# watchdog.net
KiCad netlist of a schematic drawn in Altium Designer
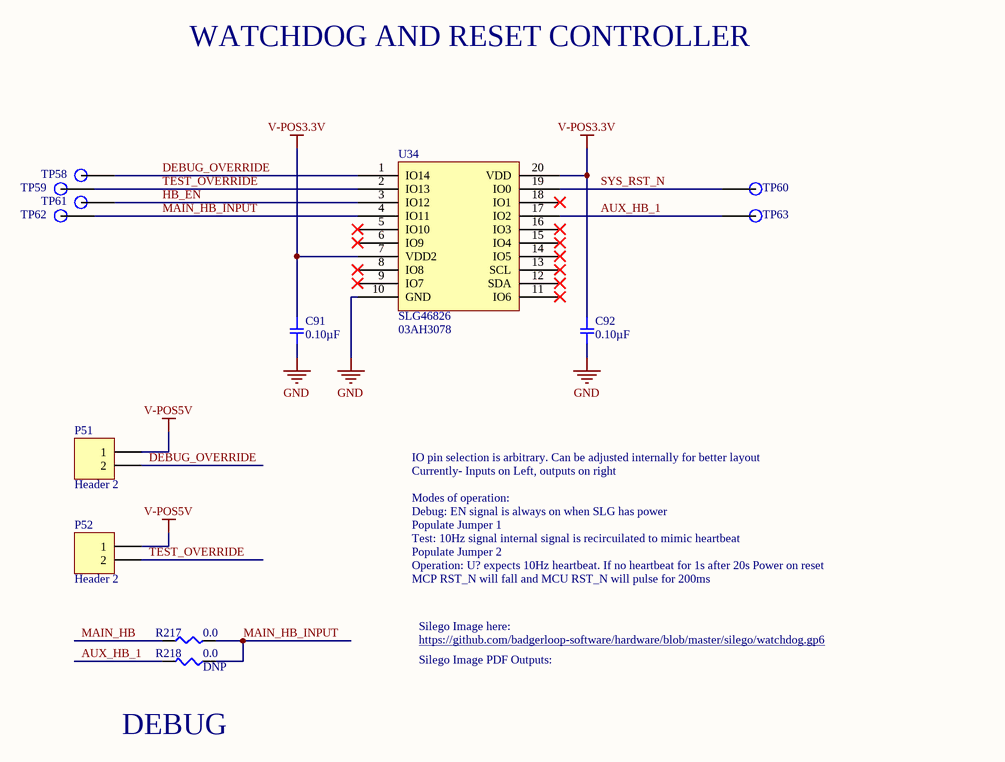
[diagram p0: watchdog.SchDoc]

(export (version "E")
  (design (tool "Eeschema 10.0.6"))
  (components
    (comp (ref "C91")
      (value "0.10µF")
      (footprint "SMD-0805C")
      (description "CAP CER 0.1UF 25V X7R 0805")
      (fields
        (field (name "DIGI-KEY PART NUMBER") "490-12754-1-ND")
        (field (name "PART NUMBER") "GRM219R71E104KA01D")
      )
      (libsource (lib "capacitors") (part "GRM219R71E104KA01D"))
    )
    (comp (ref "C92")
      (value "0.10µF")
      (footprint "SMD-0805C")
      (description "CAP CER 0.1UF 25V X7R 0805")
      (fields
        (field (name "DIGI-KEY PART NUMBER") "490-12754-1-ND")
        (field (name "PART NUMBER") "GRM219R71E104KA01D")
      )
      (libsource (lib "capacitors") (part "GRM219R71E104KA01D"))
    )
    (comp (ref "P51")
      (value "Header 2")
      (footprint "Pin Header 1x2 TH Pitch 2.54mm")
      (description "Header, 2-Pin")
      (fields (field (name "PUBLISHER") "Altium Limited"))
      (libsource (lib "connector") (part "Header 2"))
    )
    (comp (ref "P52")
      (value "Header 2")
      (footprint "Pin Header 1x2 TH Pitch 2.54mm")
      (description "Header, 2-Pin")
      (fields (field (name "PUBLISHER") "Altium Limited"))
      (libsource (lib "connector") (part "Header 2"))
    )
    (comp (ref "R217")
      (value "0.0")
      (footprint "SMD-0805-RES")
      (description "RES SMD 0.0 OHM JUMPER 1/8W 0805")
      (fields (field (name "PART NUMBER") "ERJ-6GEY0R00V") (field (name "DIGI-KEY PART NUMBER") "P0.0ACT-ND"))
      (libsource (lib "resistors") (part "ERJ-6GEY0R00V"))
    )
    (comp (ref "R218")
      (value "0.0")
      (footprint "SMD-0805-RES")
      (description "RES SMD 0.0 OHM JUMPER 1/8W 0805")
      (fields
        (field (name "PART NUMBER") "ERJ-6GEY0R00V")
        (field (name "DIGI-KEY PART NUMBER") "P0.0ACT-ND")
        (field (name "DNP") "DNP")
      )
      (libsource (lib "resistors") (part "ERJ-6GEY0R00V"))
    )
    (comp (ref "TP58")
      (value "TP")
      (footprint "Test Point")
      (description "SMD TEST POINT")
      (libsource (lib "misc") (part "TP"))
    )
    (comp (ref "TP59")
      (value "TP")
      (footprint "Test Point")
      (description "SMD TEST POINT")
      (libsource (lib "misc") (part "TP"))
    )
    (comp (ref "TP60")
      (value "TP")
      (footprint "Test Point")
      (description "SMD TEST POINT")
      (libsource (lib "misc") (part "TP"))
    )
    (comp (ref "TP61")
      (value "TP")
      (footprint "Test Point")
      (description "SMD TEST POINT")
      (libsource (lib "misc") (part "TP"))
    )
    (comp (ref "TP62")
      (value "TP")
      (footprint "Test Point")
      (description "SMD TEST POINT")
      (libsource (lib "misc") (part "TP"))
    )
    (comp (ref "TP63")
      (value "TP")
      (footprint "Test Point")
      (description "SMD TEST POINT")
      (libsource (lib "misc") (part "TP"))
    )
    (comp (ref "U34")
      (value "SLG46826")
      (footprint "SOP65P640X175-20N")
      (description "GreenPAK Programmable Mixed Signal Matrix with In-System Programmability")
      (fields
        (field (name "MANUFACTURER") "Dialog Semiconductor")
        (field (name "MANUFACTURER PART NUMBER") "SLG46826V-SKT")
        (field (name "SUPPLIER PART NUMBER 1") "03AH3078")
      )
      (libsource (lib "ic") (part "SLG46826"))
    )
  )
  (nets
    (net (code "1") (name "/AUX_HB_1") (class "Default")
      (node (ref "R218") (pin "2") (pinfunction "2_2") (pintype "passive"))
      (node (ref "TP63") (pin "1") (pinfunction "1_1") (pintype "passive"))
      (node (ref "U34") (pin "17") (pinfunction "IO2_17") (pintype "passive"))
    )
    (net (code "2") (name "/DEBUG_OVERRIDE") (class "Default")
      (node (ref "P51") (pin "2") (pinfunction "2_2") (pintype "passive"))
      (node (ref "TP58") (pin "1") (pinfunction "1_1") (pintype "passive"))
      (node (ref "U34") (pin "1") (pinfunction "IO14_1") (pintype "passive"))
    )
    (net (code "3") (name "/HB_EN") (class "Default")
      (node (ref "TP61") (pin "1") (pinfunction "1_1") (pintype "passive"))
      (node (ref "U34") (pin "3") (pinfunction "IO12_3") (pintype "passive"))
    )
    (net (code "4") (name "/MAIN_HB") (class "Default")
      (node (ref "R217") (pin "1") (pinfunction "1_1") (pintype "passive"))
    )
    (net (code "5") (name "/MAIN_HB_INPUT") (class "Default")
      (node (ref "R217") (pin "2") (pinfunction "2_2") (pintype "passive"))
      (node (ref "R218") (pin "1") (pinfunction "1_1") (pintype "passive"))
      (node (ref "TP62") (pin "1") (pinfunction "1_1") (pintype "passive"))
      (node (ref "U34") (pin "4") (pinfunction "IO11_4") (pintype "passive"))
    )
    (net (code "6") (name "/SYS_RST_N") (class "Default")
      (node (ref "TP60") (pin "1") (pinfunction "1_1") (pintype "passive"))
      (node (ref "U34") (pin "19") (pinfunction "IO0_19") (pintype "passive"))
    )
    (net (code "7") (name "/TEST_OVERRIDE") (class "Default")
      (node (ref "P52") (pin "2") (pinfunction "2_2") (pintype "passive"))
      (node (ref "TP59") (pin "1") (pinfunction "1_1") (pintype "passive"))
      (node (ref "U34") (pin "2") (pinfunction "IO13_2") (pintype "passive"))
    )
    (net (code "8") (name "GND") (class "Default")
      (node (ref "C91") (pin "2") (pinfunction "2_2") (pintype "passive"))
      (node (ref "C92") (pin "2") (pinfunction "2_2") (pintype "passive"))
      (node (ref "U34") (pin "10") (pinfunction "GND_10") (pintype "passive"))
    )
    (net (code "9") (name "V-POS3.3V") (class "Default")
      (node (ref "C91") (pin "1") (pinfunction "1_1") (pintype "passive"))
      (node (ref "C92") (pin "1") (pinfunction "1_1") (pintype "passive"))
      (node (ref "U34") (pin "20") (pinfunction "VDD_20") (pintype "passive"))
      (node (ref "U34") (pin "7") (pinfunction "VDD2_7") (pintype "passive"))
    )
    (net (code "10") (name "V-POS5V") (class "Default")
      (node (ref "P51") (pin "1") (pinfunction "1_1") (pintype "passive"))
      (node (ref "P52") (pin "1") (pinfunction "1_1") (pintype "passive"))
    )
    (net (code "11") (name "unconnected-(U34-IO1-Pad18)") (class "Default")
      (node (ref "U34") (pin "18") (pinfunction "IO1_18") (pintype "passive+no_connect"))
    )
    (net (code "12") (name "unconnected-(U34-IO3-Pad16)") (class "Default")
      (node (ref "U34") (pin "16") (pinfunction "IO3_16") (pintype "passive+no_connect"))
    )
    (net (code "13") (name "unconnected-(U34-IO4-Pad15)") (class "Default")
      (node (ref "U34") (pin "15") (pinfunction "IO4_15") (pintype "passive+no_connect"))
    )
    (net (code "14") (name "unconnected-(U34-IO5-Pad14)") (class "Default")
      (node (ref "U34") (pin "14") (pinfunction "IO5_14") (pintype "passive+no_connect"))
    )
    (net (code "15") (name "unconnected-(U34-IO6-Pad11)") (class "Default")
      (node (ref "U34") (pin "11") (pinfunction "IO6_11") (pintype "passive+no_connect"))
    )
    (net (code "16") (name "unconnected-(U34-IO7-Pad9)") (class "Default")
      (node (ref "U34") (pin "9") (pinfunction "IO7_9") (pintype "passive+no_connect"))
    )
    (net (code "17") (name "unconnected-(U34-IO8-Pad8)") (class "Default")
      (node (ref "U34") (pin "8") (pinfunction "IO8_8") (pintype "passive+no_connect"))
    )
    (net (code "18") (name "unconnected-(U34-IO9-Pad6)") (class "Default")
      (node (ref "U34") (pin "6") (pinfunction "IO9_6") (pintype "passive+no_connect"))
    )
    (net (code "19") (name "unconnected-(U34-IO10-Pad5)") (class "Default")
      (node (ref "U34") (pin "5") (pinfunction "IO10_5") (pintype "passive+no_connect"))
    )
    (net (code "20") (name "unconnected-(U34-SCL-Pad13)") (class "Default")
      (node (ref "U34") (pin "13") (pinfunction "SCL_13") (pintype "passive+no_connect"))
    )
    (net (code "21") (name "unconnected-(U34-SDA-Pad12)") (class "Default")
      (node (ref "U34") (pin "12") (pinfunction "SDA_12") (pintype "passive+no_connect"))
    )
  )
)
